# masterclock.net
KiCad netlist of a schematic drawn in EAGLE
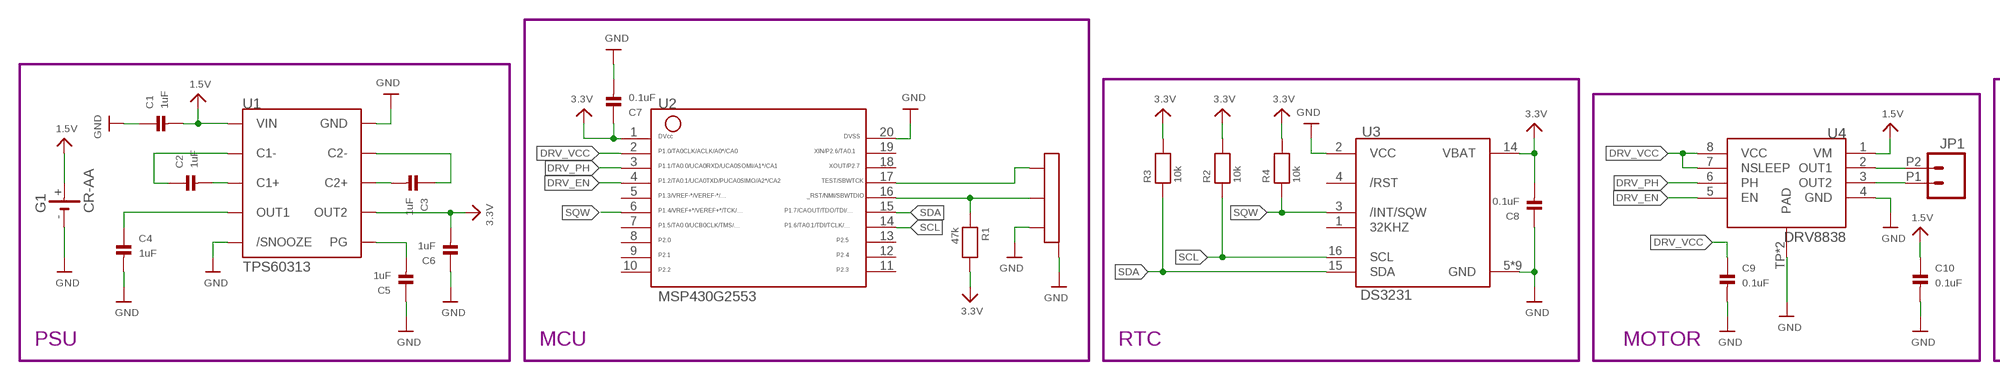
[diagram p0: schematic, sheet 1, part 1 of 2]
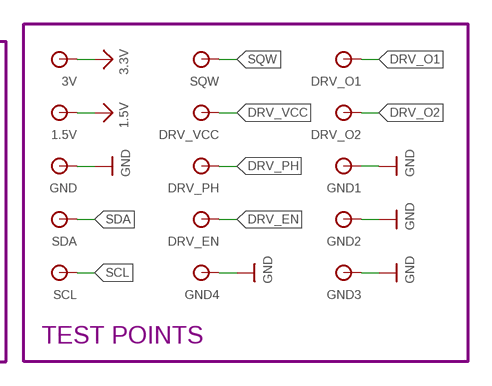
[diagram p1: schematic, sheet 1, part 2 of 2]

(export (version "E")
  (design (tool "Eeschema 10.0.6"))
  (components
    (comp (ref "1.5V")
      (value "TESTPAD")
      (footprint "eagle-import:TESTPAD")
      (libsource (lib "eagle-import") (part "TESTPAD"))
    )
    (comp (ref "3V")
      (value "TESTPAD")
      (footprint "eagle-import:TESTPAD")
      (libsource (lib "eagle-import") (part "TESTPAD"))
    )
    (comp (ref "C1")
      (value "1uF")
      (footprint "eagle-import:0402")
      (libsource (lib "eagle-import") (part "CAP_CERAMIC0402"))
    )
    (comp (ref "C2")
      (value "1uF")
      (footprint "eagle-import:0402")
      (libsource (lib "eagle-import") (part "CAP_CERAMIC0402"))
    )
    (comp (ref "C3")
      (value "1uF")
      (footprint "eagle-import:0402")
      (libsource (lib "eagle-import") (part "CAP_CERAMIC0402"))
    )
    (comp (ref "C4")
      (value "1uF")
      (footprint "eagle-import:0402")
      (libsource (lib "eagle-import") (part "CAP_CERAMIC0402"))
    )
    (comp (ref "C5")
      (value "1uF")
      (footprint "eagle-import:0402")
      (libsource (lib "eagle-import") (part "CAP_CERAMIC0402"))
    )
    (comp (ref "C6")
      (value "1uF")
      (footprint "eagle-import:0402")
      (libsource (lib "eagle-import") (part "CAP_CERAMIC0402"))
    )
    (comp (ref "C7")
      (value "0.1uF")
      (footprint "eagle-import:0402")
      (libsource (lib "eagle-import") (part "CAP_CERAMIC0402"))
    )
    (comp (ref "C8")
      (value "0.1uF")
      (footprint "eagle-import:0402")
      (libsource (lib "eagle-import") (part "CAP_CERAMIC0402"))
    )
    (comp (ref "C9")
      (value "0.1uF")
      (footprint "eagle-import:0402")
      (libsource (lib "eagle-import") (part "CAP_CERAMIC0402"))
    )
    (comp (ref "C10")
      (value "0.1uF")
      (footprint "eagle-import:0402")
      (libsource (lib "eagle-import") (part "CAP_CERAMIC0402"))
    )
    (comp (ref "DRV_EN")
      (value "TESTPAD")
      (footprint "eagle-import:TESTPAD")
      (libsource (lib "eagle-import") (part "TESTPAD"))
    )
    (comp (ref "DRV_O1")
      (value "TESTPAD")
      (footprint "eagle-import:TESTPAD")
      (libsource (lib "eagle-import") (part "TESTPAD"))
    )
    (comp (ref "DRV_O2")
      (value "TESTPAD")
      (footprint "eagle-import:TESTPAD")
      (libsource (lib "eagle-import") (part "TESTPAD"))
    )
    (comp (ref "DRV_PH")
      (value "TESTPAD")
      (footprint "eagle-import:TESTPAD")
      (libsource (lib "eagle-import") (part "TESTPAD"))
    )
    (comp (ref "DRV_VCC")
      (value "TESTPAD")
      (footprint "eagle-import:TESTPAD")
      (libsource (lib "eagle-import") (part "TESTPAD"))
    )
    (comp (ref "G1")
      (value "CR-AA")
      (footprint "eagle-import:CRAA")
      (libsource (lib "eagle-import") (part "CR-AA"))
    )
    (comp (ref "GND")
      (value "TESTPAD")
      (footprint "eagle-import:TESTPAD")
      (libsource (lib "eagle-import") (part "TESTPAD"))
    )
    (comp (ref "GND1")
      (value "GND")
      (footprint "eagle-import:TESTPAD")
      (libsource (lib "eagle-import") (part "TESTPAD"))
    )
    (comp (ref "GND2")
      (value "GND")
      (footprint "eagle-import:TESTPAD")
      (libsource (lib "eagle-import") (part "TESTPAD"))
    )
    (comp (ref "GND3")
      (value "GND")
      (footprint "eagle-import:TESTPAD")
      (libsource (lib "eagle-import") (part "TESTPAD"))
    )
    (comp (ref "GND4")
      (value "GND")
      (footprint "eagle-import:TESTPAD")
      (libsource (lib "eagle-import") (part "TESTPAD"))
    )
    (comp (ref "JP1")
      (value "M022.54MM_SCREWTERM")
      (footprint "eagle-import:1X02_2.54_SCREWTERM")
      (libsource (lib "eagle-import") (part "M022.54MM_SCREWTERM"))
    )
    (comp (ref "R1")
      (value "47k")
      (footprint "eagle-import:0402")
      (libsource (lib "eagle-import") (part "RESISTOR0402"))
    )
    (comp (ref "R2")
      (value "10k")
      (footprint "eagle-import:0402")
      (libsource (lib "eagle-import") (part "RESISTOR0402"))
    )
    (comp (ref "R3")
      (value "10k")
      (footprint "eagle-import:0402")
      (libsource (lib "eagle-import") (part "RESISTOR0402"))
    )
    (comp (ref "R4")
      (value "10k")
      (footprint "eagle-import:0402")
      (libsource (lib "eagle-import") (part "RESISTOR0402"))
    )
    (comp (ref "SCL")
      (value "TESTPAD")
      (footprint "eagle-import:TESTPAD")
      (libsource (lib "eagle-import") (part "TESTPAD"))
    )
    (comp (ref "SDA")
      (value "TESTPAD")
      (footprint "eagle-import:TESTPAD")
      (libsource (lib "eagle-import") (part "TESTPAD"))
    )
    (comp (ref "SQW")
      (value "TESTPAD")
      (footprint "eagle-import:TESTPAD")
      (libsource (lib "eagle-import") (part "TESTPAD"))
    )
    (comp (ref "U$27")
      (value "M03")
      (footprint "eagle-import:TE-MICRO-MNL-")
      (libsource (lib "eagle-import") (part "M03"))
    )
    (comp (ref "U1")
      (value "TPS60313")
      (footprint "eagle-import:MSOP10")
      (libsource (lib "eagle-import") (part "TPS60313"))
    )
    (comp (ref "U2")
      (value "MSP430G2553")
      (footprint "eagle-import:PW20")
      (libsource (lib "eagle-import") (part "MSP430G2553"))
    )
    (comp (ref "U3")
      (value "DS3231")
      (footprint "eagle-import:SO16")
      (libsource (lib "eagle-import") (part "DS3231"))
    )
    (comp (ref "U4")
      (value "DRV8838")
      (footprint "eagle-import:WSON8")
      (libsource (lib "eagle-import") (part "DRV8838"))
    )
  )
  (nets
    (net (code "1") (name "1.5V") (class "Default")
      (node (ref "1.5V") (pin "P$1") (pinfunction "P$1_P$1") (pintype "bidirectional"))
      (node (ref "C1") (pin "2") (pinfunction "P$2_2") (pintype "passive"))
      (node (ref "C10") (pin "1") (pinfunction "P$1_1") (pintype "passive"))
      (node (ref "G1") (pin "+") (pinfunction "+_+") (pintype "passive"))
      (node (ref "U1") (pin "P$3") (pinfunction "VIN_P$3") (pintype "power_in"))
      (node (ref "U4") (pin "1") (pinfunction "VM_1") (pintype "bidirectional"))
    )
    (net (code "2") (name "3.3V") (class "Default")
      (node (ref "3V") (pin "P$1") (pinfunction "P$1_P$1") (pintype "bidirectional"))
      (node (ref "C6") (pin "2") (pinfunction "P$2_2") (pintype "passive"))
      (node (ref "C7") (pin "1") (pinfunction "P$1_1") (pintype "passive"))
      (node (ref "C8") (pin "2") (pinfunction "P$2_2") (pintype "passive"))
      (node (ref "R1") (pin "2") (pinfunction "2_2") (pintype "passive"))
      (node (ref "R2") (pin "2") (pinfunction "2_2") (pintype "passive"))
      (node (ref "R3") (pin "2") (pinfunction "2_2") (pintype "passive"))
      (node (ref "R4") (pin "2") (pinfunction "2_2") (pintype "passive"))
      (node (ref "U1") (pin "P$6") (pinfunction "OUT2_P$6") (pintype "bidirectional"))
      (node (ref "U2") (pin "1") (pinfunction "1_1") (pintype "bidirectional"))
      (node (ref "U3") (pin "14") (pinfunction "VBAT_14") (pintype "bidirectional"))
    )
    (net (code "3") (name "DRV_EN") (class "Default")
      (node (ref "DRV_EN") (pin "P$1") (pinfunction "P$1_P$1") (pintype "bidirectional"))
      (node (ref "U2") (pin "4") (pinfunction "4_4") (pintype "bidirectional"))
      (node (ref "U4") (pin "5") (pinfunction "EN_5") (pintype "bidirectional"))
    )
    (net (code "4") (name "DRV_O1") (class "Default")
      (node (ref "DRV_O1") (pin "P$1") (pinfunction "P$1_P$1") (pintype "bidirectional"))
      (node (ref "JP1") (pin "P2") (pinfunction "2_P2") (pintype "passive"))
      (node (ref "U4") (pin "2") (pinfunction "OUT1_2") (pintype "bidirectional"))
    )
    (net (code "5") (name "DRV_O2") (class "Default")
      (node (ref "DRV_O2") (pin "P$1") (pinfunction "P$1_P$1") (pintype "bidirectional"))
      (node (ref "JP1") (pin "P1") (pinfunction "1_P1") (pintype "passive"))
      (node (ref "U4") (pin "3") (pinfunction "OUT2_3") (pintype "bidirectional"))
    )
    (net (code "6") (name "DRV_PH") (class "Default")
      (node (ref "DRV_PH") (pin "P$1") (pinfunction "P$1_P$1") (pintype "bidirectional"))
      (node (ref "U2") (pin "3") (pinfunction "3_3") (pintype "bidirectional"))
      (node (ref "U4") (pin "6") (pinfunction "PH_6") (pintype "bidirectional"))
    )
    (net (code "7") (name "DRV_VCC") (class "Default")
      (node (ref "C9") (pin "1") (pinfunction "P$1_1") (pintype "passive"))
      (node (ref "DRV_VCC") (pin "P$1") (pinfunction "P$1_P$1") (pintype "bidirectional"))
      (node (ref "U2") (pin "2") (pinfunction "2_2") (pintype "bidirectional"))
      (node (ref "U4") (pin "7") (pinfunction "NSLEEP_7") (pintype "bidirectional"))
      (node (ref "U4") (pin "8") (pinfunction "VCC_8") (pintype "bidirectional"))
    )
    (net (code "8") (name "GND") (class "Default")
      (node (ref "C1") (pin "1") (pinfunction "P$1_1") (pintype "passive"))
      (node (ref "C10") (pin "2") (pinfunction "P$2_2") (pintype "passive"))
      (node (ref "C4") (pin "2") (pinfunction "P$2_2") (pintype "passive"))
      (node (ref "C5") (pin "1") (pinfunction "P$1_1") (pintype "passive"))
      (node (ref "C6") (pin "1") (pinfunction "P$1_1") (pintype "passive"))
      (node (ref "C7") (pin "2") (pinfunction "P$2_2") (pintype "passive"))
      (node (ref "C8") (pin "1") (pinfunction "P$1_1") (pintype "passive"))
      (node (ref "C9") (pin "2") (pinfunction "P$2_2") (pintype "passive"))
      (node (ref "G1") (pin "-") (pinfunction "-_-") (pintype "passive"))
      (node (ref "GND") (pin "P$1") (pinfunction "P$1_P$1") (pintype "bidirectional"))
      (node (ref "GND1") (pin "P$1") (pinfunction "P$1_P$1") (pintype "bidirectional"))
      (node (ref "GND2") (pin "P$1") (pinfunction "P$1_P$1") (pintype "bidirectional"))
      (node (ref "GND3") (pin "P$1") (pinfunction "P$1_P$1") (pintype "bidirectional"))
      (node (ref "GND4") (pin "P$1") (pinfunction "P$1_P$1") (pintype "bidirectional"))
      (node (ref "U$27") (pin "H1") (pinfunction "P$4_H1") (pintype "bidirectional"))
      (node (ref "U$27") (pin "H2") (pinfunction "P$4_H2") (pintype "bidirectional"))
      (node (ref "U$27") (pin "P$3") (pinfunction "P$3_P$3") (pintype "bidirectional"))
      (node (ref "U1") (pin "P$1") (pinfunction "/SNOOZE_P$1") (pintype "bidirectional"))
      (node (ref "U1") (pin "P$9") (pinfunction "GND_P$9") (pintype "power_in"))
      (node (ref "U2") (pin "20") (pinfunction "20_20") (pintype "bidirectional"))
      (node (ref "U3") (pin "10") (pinfunction "GND_10") (pintype "bidirectional"))
      (node (ref "U3") (pin "11") (pinfunction "GND_11") (pintype "bidirectional"))
      (node (ref "U3") (pin "12") (pinfunction "GND_12") (pintype "bidirectional"))
      (node (ref "U3") (pin "13") (pinfunction "GND_13") (pintype "bidirectional"))
      (node (ref "U3") (pin "2") (pinfunction "VCC_2") (pintype "bidirectional"))
      (node (ref "U3") (pin "5") (pinfunction "GND_5") (pintype "bidirectional"))
      (node (ref "U3") (pin "6") (pinfunction "GND_6") (pintype "bidirectional"))
      (node (ref "U3") (pin "7") (pinfunction "GND_7") (pintype "bidirectional"))
      (node (ref "U3") (pin "8") (pinfunction "GND_8") (pintype "bidirectional"))
      (node (ref "U3") (pin "9") (pinfunction "GND_9") (pintype "bidirectional"))
      (node (ref "U4") (pin "4") (pinfunction "GND_4") (pintype "bidirectional"))
      (node (ref "U4") (pin "TP") (pinfunction "PAD_TP") (pintype "bidirectional"))
      (node (ref "U4") (pin "TP1") (pinfunction "PAD_TP1") (pintype "bidirectional"))
    )
    (net (code "9") (name "Net-(C2-P$1)") (class "Default")
      (node (ref "C2") (pin "1") (pinfunction "P$1_1") (pintype "passive"))
      (node (ref "U1") (pin "P$2") (pinfunction "C1-_P$2") (pintype "bidirectional"))
    )
    (net (code "10") (name "Net-(C2-P$2)") (class "Default")
      (node (ref "C2") (pin "2") (pinfunction "P$2_2") (pintype "passive"))
      (node (ref "U1") (pin "P$4") (pinfunction "C1+_P$4") (pintype "bidirectional"))
    )
    (net (code "11") (name "Net-(C3-P$1)") (class "Default")
      (node (ref "C3") (pin "1") (pinfunction "P$1_1") (pintype "passive"))
      (node (ref "U1") (pin "P$8") (pinfunction "C2-_P$8") (pintype "bidirectional"))
    )
    (net (code "12") (name "Net-(C3-P$2)") (class "Default")
      (node (ref "C3") (pin "2") (pinfunction "P$2_2") (pintype "passive"))
      (node (ref "U1") (pin "P$7") (pinfunction "C2+_P$7") (pintype "bidirectional"))
    )
    (net (code "13") (name "Net-(C4-P$1)") (class "Default")
      (node (ref "C4") (pin "1") (pinfunction "P$1_1") (pintype "passive"))
      (node (ref "U1") (pin "P$5") (pinfunction "OUT1_P$5") (pintype "bidirectional"))
    )
    (net (code "14") (name "Net-(C5-P$2)") (class "Default")
      (node (ref "C5") (pin "2") (pinfunction "P$2_2") (pintype "passive"))
      (node (ref "U1") (pin "P$10") (pinfunction "PG_P$10") (pintype "bidirectional"))
    )
    (net (code "15") (name "Net-(R1-Pad1)") (class "Default")
      (node (ref "R1") (pin "1") (pinfunction "1_1") (pintype "passive"))
      (node (ref "U$27") (pin "P$2") (pinfunction "P$2_P$2") (pintype "bidirectional"))
      (node (ref "U2") (pin "16") (pinfunction "16_16") (pintype "bidirectional"))
    )
    (net (code "16") (name "Net-(U$27-PadP$1)") (class "Default")
      (node (ref "U$27") (pin "P$1") (pinfunction "P$1_P$1") (pintype "bidirectional"))
      (node (ref "U2") (pin "17") (pinfunction "17_17") (pintype "bidirectional"))
    )
    (net (code "17") (name "SCL") (class "Default")
      (node (ref "R2") (pin "1") (pinfunction "1_1") (pintype "passive"))
      (node (ref "SCL") (pin "P$1") (pinfunction "P$1_P$1") (pintype "bidirectional"))
      (node (ref "U2") (pin "14") (pinfunction "14_14") (pintype "bidirectional"))
      (node (ref "U3") (pin "16") (pinfunction "SCL_16") (pintype "bidirectional"))
    )
    (net (code "18") (name "SDA") (class "Default")
      (node (ref "R3") (pin "1") (pinfunction "1_1") (pintype "passive"))
      (node (ref "SDA") (pin "P$1") (pinfunction "P$1_P$1") (pintype "bidirectional"))
      (node (ref "U2") (pin "15") (pinfunction "15_15") (pintype "bidirectional"))
      (node (ref "U3") (pin "15") (pinfunction "SDA_15") (pintype "bidirectional"))
    )
    (net (code "19") (name "SQW") (class "Default")
      (node (ref "R4") (pin "1") (pinfunction "1_1") (pintype "passive"))
      (node (ref "SQW") (pin "P$1") (pinfunction "P$1_P$1") (pintype "bidirectional"))
      (node (ref "U2") (pin "6") (pinfunction "6_6") (pintype "bidirectional"))
      (node (ref "U3") (pin "3") (pinfunction "/INT/SQW_3") (pintype "bidirectional"))
    )
    (net (code "20") (name "unconnected-(U2-Pad5)") (class "Default")
      (node (ref "U2") (pin "5") (pinfunction "5_5") (pintype "bidirectional"))
    )
    (net (code "21") (name "unconnected-(U2-Pad7)") (class "Default")
      (node (ref "U2") (pin "7") (pinfunction "7_7") (pintype "bidirectional"))
    )
    (net (code "22") (name "unconnected-(U2-Pad8)") (class "Default")
      (node (ref "U2") (pin "8") (pinfunction "8_8") (pintype "bidirectional"))
    )
    (net (code "23") (name "unconnected-(U2-Pad9)") (class "Default")
      (node (ref "U2") (pin "9") (pinfunction "9_9") (pintype "bidirectional"))
    )
    (net (code "24") (name "unconnected-(U2-Pad10)") (class "Default")
      (node (ref "U2") (pin "10") (pinfunction "10_10") (pintype "bidirectional"))
    )
    (net (code "25") (name "unconnected-(U2-Pad11)") (class "Default")
      (node (ref "U2") (pin "11") (pinfunction "11_11") (pintype "bidirectional"))
    )
    (net (code "26") (name "unconnected-(U2-Pad12)") (class "Default")
      (node (ref "U2") (pin "12") (pinfunction "12_12") (pintype "bidirectional"))
    )
    (net (code "27") (name "unconnected-(U2-Pad13)") (class "Default")
      (node (ref "U2") (pin "13") (pinfunction "13_13") (pintype "bidirectional"))
    )
    (net (code "28") (name "unconnected-(U2-Pad18)") (class "Default")
      (node (ref "U2") (pin "18") (pinfunction "18_18") (pintype "bidirectional"))
    )
    (net (code "29") (name "unconnected-(U2-Pad19)") (class "Default")
      (node (ref "U2") (pin "19") (pinfunction "19_19") (pintype "bidirectional"))
    )
    (net (code "30") (name "unconnected-(U3-32KHZ-Pad1)") (class "Default")
      (node (ref "U3") (pin "1") (pinfunction "32KHZ_1") (pintype "bidirectional"))
    )
    (net (code "31") (name "unconnected-(U3-{slash}RST-Pad4)") (class "Default")
      (node (ref "U3") (pin "4") (pinfunction "/RST_4") (pintype "bidirectional"))
    )
  )
)
